# ALU_AND.net
KiCad netlist of a schematic drawn in Altium Designer
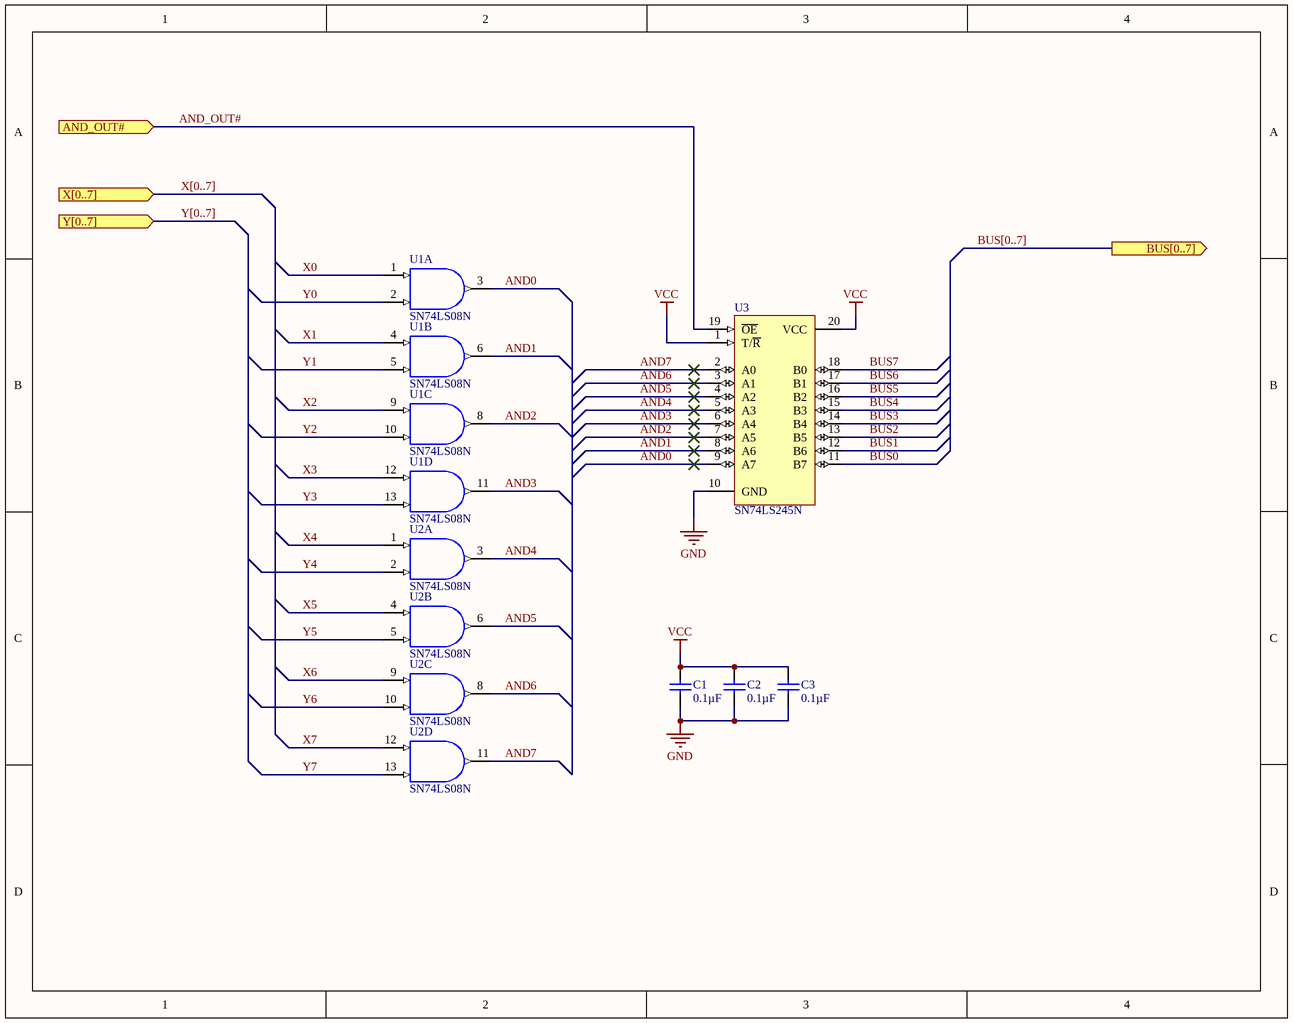
[diagram p0: ALU_AND.SchDoc]

(export (version "E")
  (design (tool "Eeschema 10.0.6"))
  (components
    (comp (ref "C1")
      (value "K104K15X7RF5TL2")
      (footprint "VISH-K104K15X7RF5TL2")
      (description "Ceramic Capacitor, 100 nF, +/- 10%, 50 V, -55 to 125 degC, 2-Pin THD, RoHS, Tape and Reel")
      (fields
        (field (name "MANUFACTURER") "Vishay")
        (field (name "TOLERANCE") "±10%")
        (field (name "CAPACITANCE") "0.1µF")
      )
      (libsource (lib "Altium Content Vault") (part "CAP-NP-2"))
    )
    (comp (ref "C2")
      (value "K104K15X7RF5TL2")
      (footprint "VISH-K104K15X7RF5TL2")
      (description "Ceramic Capacitor, 100 nF, +/- 10%, 50 V, -55 to 125 degC, 2-Pin THD, RoHS, Tape and Reel")
      (fields
        (field (name "MANUFACTURER") "Vishay")
        (field (name "TOLERANCE") "±10%")
        (field (name "CAPACITANCE") "0.1µF")
      )
      (libsource (lib "Altium Content Vault") (part "CAP-NP-2"))
    )
    (comp (ref "C3")
      (value "K104K15X7RF5TL2")
      (footprint "VISH-K104K15X7RF5TL2")
      (description "Ceramic Capacitor, 100 nF, +/- 10%, 50 V, -55 to 125 degC, 2-Pin THD, RoHS, Tape and Reel")
      (fields
        (field (name "MANUFACTURER") "Vishay")
        (field (name "TOLERANCE") "±10%")
        (field (name "CAPACITANCE") "0.1µF")
      )
      (libsource (lib "Altium Content Vault") (part "CAP-NP-2"))
    )
    (comp (ref "U1")
      (value "SN74LS08N")
      (footprint "N014")
      (description "Quadruple 2-Input Positive-AND Gate")
      (fields (field (name "PUBLISHER") "Altium Limited"))
      (libsource (lib "TI Logic Gate 2") (part "SN74LS08N"))
    )
    (comp (ref "U2")
      (value "SN74LS08N")
      (footprint "N014")
      (description "Quadruple 2-Input Positive-AND Gate")
      (fields (field (name "PUBLISHER") "Altium Limited"))
      (libsource (lib "TI Logic Gate 2") (part "SN74LS08N"))
    )
    (comp (ref "U3")
      (value "SN74LS245N")
      (footprint "N020")
      (description "Octal Bus Transceiver with 3-State Outputs")
      (fields (field (name "PUBLISHER") "Altium Limited"))
      (libsource (lib "TI Interface 8-Bit Line Transceiver") (part "SN74LS245N"))
    )
  )
  (nets
    (net (code "1") (name "/AND0") (class "Default")
      (node (ref "U1") (pin "3") (pinfunction "Y_3") (pintype "output"))
      (node (ref "U3") (pin "9") (pinfunction "A7_9") (pintype "bidirectional"))
    )
    (net (code "2") (name "/AND1") (class "Default")
      (node (ref "U1") (pin "6") (pinfunction "Y_6") (pintype "output"))
      (node (ref "U3") (pin "8") (pinfunction "A6_8") (pintype "bidirectional"))
    )
    (net (code "3") (name "/AND2") (class "Default")
      (node (ref "U1") (pin "8") (pinfunction "Y_8") (pintype "output"))
      (node (ref "U3") (pin "7") (pinfunction "A5_7") (pintype "bidirectional"))
    )
    (net (code "4") (name "/AND3") (class "Default")
      (node (ref "U1") (pin "11") (pinfunction "Y_11") (pintype "output"))
      (node (ref "U3") (pin "6") (pinfunction "A4_6") (pintype "bidirectional"))
    )
    (net (code "5") (name "/AND4") (class "Default")
      (node (ref "U2") (pin "3") (pinfunction "Y_3") (pintype "output"))
      (node (ref "U3") (pin "5") (pinfunction "A3_5") (pintype "bidirectional"))
    )
    (net (code "6") (name "/AND5") (class "Default")
      (node (ref "U2") (pin "6") (pinfunction "Y_6") (pintype "output"))
      (node (ref "U3") (pin "4") (pinfunction "A2_4") (pintype "bidirectional"))
    )
    (net (code "7") (name "/AND6") (class "Default")
      (node (ref "U2") (pin "8") (pinfunction "Y_8") (pintype "output"))
      (node (ref "U3") (pin "3") (pinfunction "A1_3") (pintype "bidirectional"))
    )
    (net (code "8") (name "/AND7") (class "Default")
      (node (ref "U2") (pin "11") (pinfunction "Y_11") (pintype "output"))
      (node (ref "U3") (pin "2") (pinfunction "A0_2") (pintype "bidirectional"))
    )
    (net (code "9") (name "/AND_OUT#") (class "Default")
      (node (ref "U3") (pin "19") (pinfunction "~{OE}_19") (pintype "input"))
    )
    (net (code "10") (name "/BUS0") (class "Default")
      (node (ref "U3") (pin "11") (pinfunction "B7_11") (pintype "bidirectional"))
    )
    (net (code "11") (name "/BUS1") (class "Default")
      (node (ref "U3") (pin "12") (pinfunction "B6_12") (pintype "bidirectional"))
    )
    (net (code "12") (name "/BUS2") (class "Default")
      (node (ref "U3") (pin "13") (pinfunction "B5_13") (pintype "bidirectional"))
    )
    (net (code "13") (name "/BUS3") (class "Default")
      (node (ref "U3") (pin "14") (pinfunction "B4_14") (pintype "bidirectional"))
    )
    (net (code "14") (name "/BUS4") (class "Default")
      (node (ref "U3") (pin "15") (pinfunction "B3_15") (pintype "bidirectional"))
    )
    (net (code "15") (name "/BUS5") (class "Default")
      (node (ref "U3") (pin "16") (pinfunction "B2_16") (pintype "bidirectional"))
    )
    (net (code "16") (name "/BUS6") (class "Default")
      (node (ref "U3") (pin "17") (pinfunction "B1_17") (pintype "bidirectional"))
    )
    (net (code "17") (name "/BUS7") (class "Default")
      (node (ref "U3") (pin "18") (pinfunction "B0_18") (pintype "bidirectional"))
    )
    (net (code "19") (name "/X0") (class "Default")
      (node (ref "U1") (pin "1") (pinfunction "A_1") (pintype "input"))
    )
    (net (code "20") (name "/X1") (class "Default")
      (node (ref "U1") (pin "4") (pinfunction "A_4") (pintype "input"))
    )
    (net (code "21") (name "/X2") (class "Default")
      (node (ref "U1") (pin "9") (pinfunction "A_9") (pintype "input"))
    )
    (net (code "22") (name "/X3") (class "Default")
      (node (ref "U1") (pin "12") (pinfunction "A_12") (pintype "input"))
    )
    (net (code "23") (name "/X4") (class "Default")
      (node (ref "U2") (pin "1") (pinfunction "A_1") (pintype "input"))
    )
    (net (code "24") (name "/X5") (class "Default")
      (node (ref "U2") (pin "4") (pinfunction "A_4") (pintype "input"))
    )
    (net (code "25") (name "/X6") (class "Default")
      (node (ref "U2") (pin "9") (pinfunction "A_9") (pintype "input"))
    )
    (net (code "26") (name "/X7") (class "Default")
      (node (ref "U2") (pin "12") (pinfunction "A_12") (pintype "input"))
    )
    (net (code "28") (name "/Y0") (class "Default")
      (node (ref "U1") (pin "2") (pinfunction "B_2") (pintype "input"))
    )
    (net (code "29") (name "/Y1") (class "Default")
      (node (ref "U1") (pin "5") (pinfunction "B_5") (pintype "input"))
    )
    (net (code "30") (name "/Y2") (class "Default")
      (node (ref "U1") (pin "10") (pinfunction "B_10") (pintype "input"))
    )
    (net (code "31") (name "/Y3") (class "Default")
      (node (ref "U1") (pin "13") (pinfunction "B_13") (pintype "input"))
    )
    (net (code "32") (name "/Y4") (class "Default")
      (node (ref "U2") (pin "2") (pinfunction "B_2") (pintype "input"))
    )
    (net (code "33") (name "/Y5") (class "Default")
      (node (ref "U2") (pin "5") (pinfunction "B_5") (pintype "input"))
    )
    (net (code "34") (name "/Y6") (class "Default")
      (node (ref "U2") (pin "10") (pinfunction "B_10") (pintype "input"))
    )
    (net (code "35") (name "/Y7") (class "Default")
      (node (ref "U2") (pin "13") (pinfunction "B_13") (pintype "input"))
    )
    (net (code "37") (name "GND") (class "Default")
      (node (ref "C1") (pin "2") (pinfunction "2_2") (pintype "passive"))
      (node (ref "C2") (pin "2") (pinfunction "2_2") (pintype "passive"))
      (node (ref "C3") (pin "2") (pinfunction "2_2") (pintype "passive"))
      (node (ref "U1") (pin "7") (pinfunction "GND_7") (pintype "power_in"))
      (node (ref "U2") (pin "7") (pinfunction "GND_7") (pintype "power_in"))
      (node (ref "U3") (pin "10") (pinfunction "GND_10") (pintype "power_in"))
    )
    (net (code "38") (name "VCC") (class "Default")
      (node (ref "C1") (pin "1") (pinfunction "1_1") (pintype "passive"))
      (node (ref "C2") (pin "1") (pinfunction "1_1") (pintype "passive"))
      (node (ref "C3") (pin "1") (pinfunction "1_1") (pintype "passive"))
      (node (ref "U1") (pin "14") (pinfunction "VCC_14") (pintype "power_in"))
      (node (ref "U2") (pin "14") (pinfunction "VCC_14") (pintype "power_in"))
      (node (ref "U3") (pin "1") (pinfunction "T/~{R}_1") (pintype "input"))
      (node (ref "U3") (pin "20") (pinfunction "VCC_20") (pintype "power_in"))
    )
  )
)
